# BLDC-CONTROLLET.net
KiCad netlist of a schematic drawn in Altium Designer
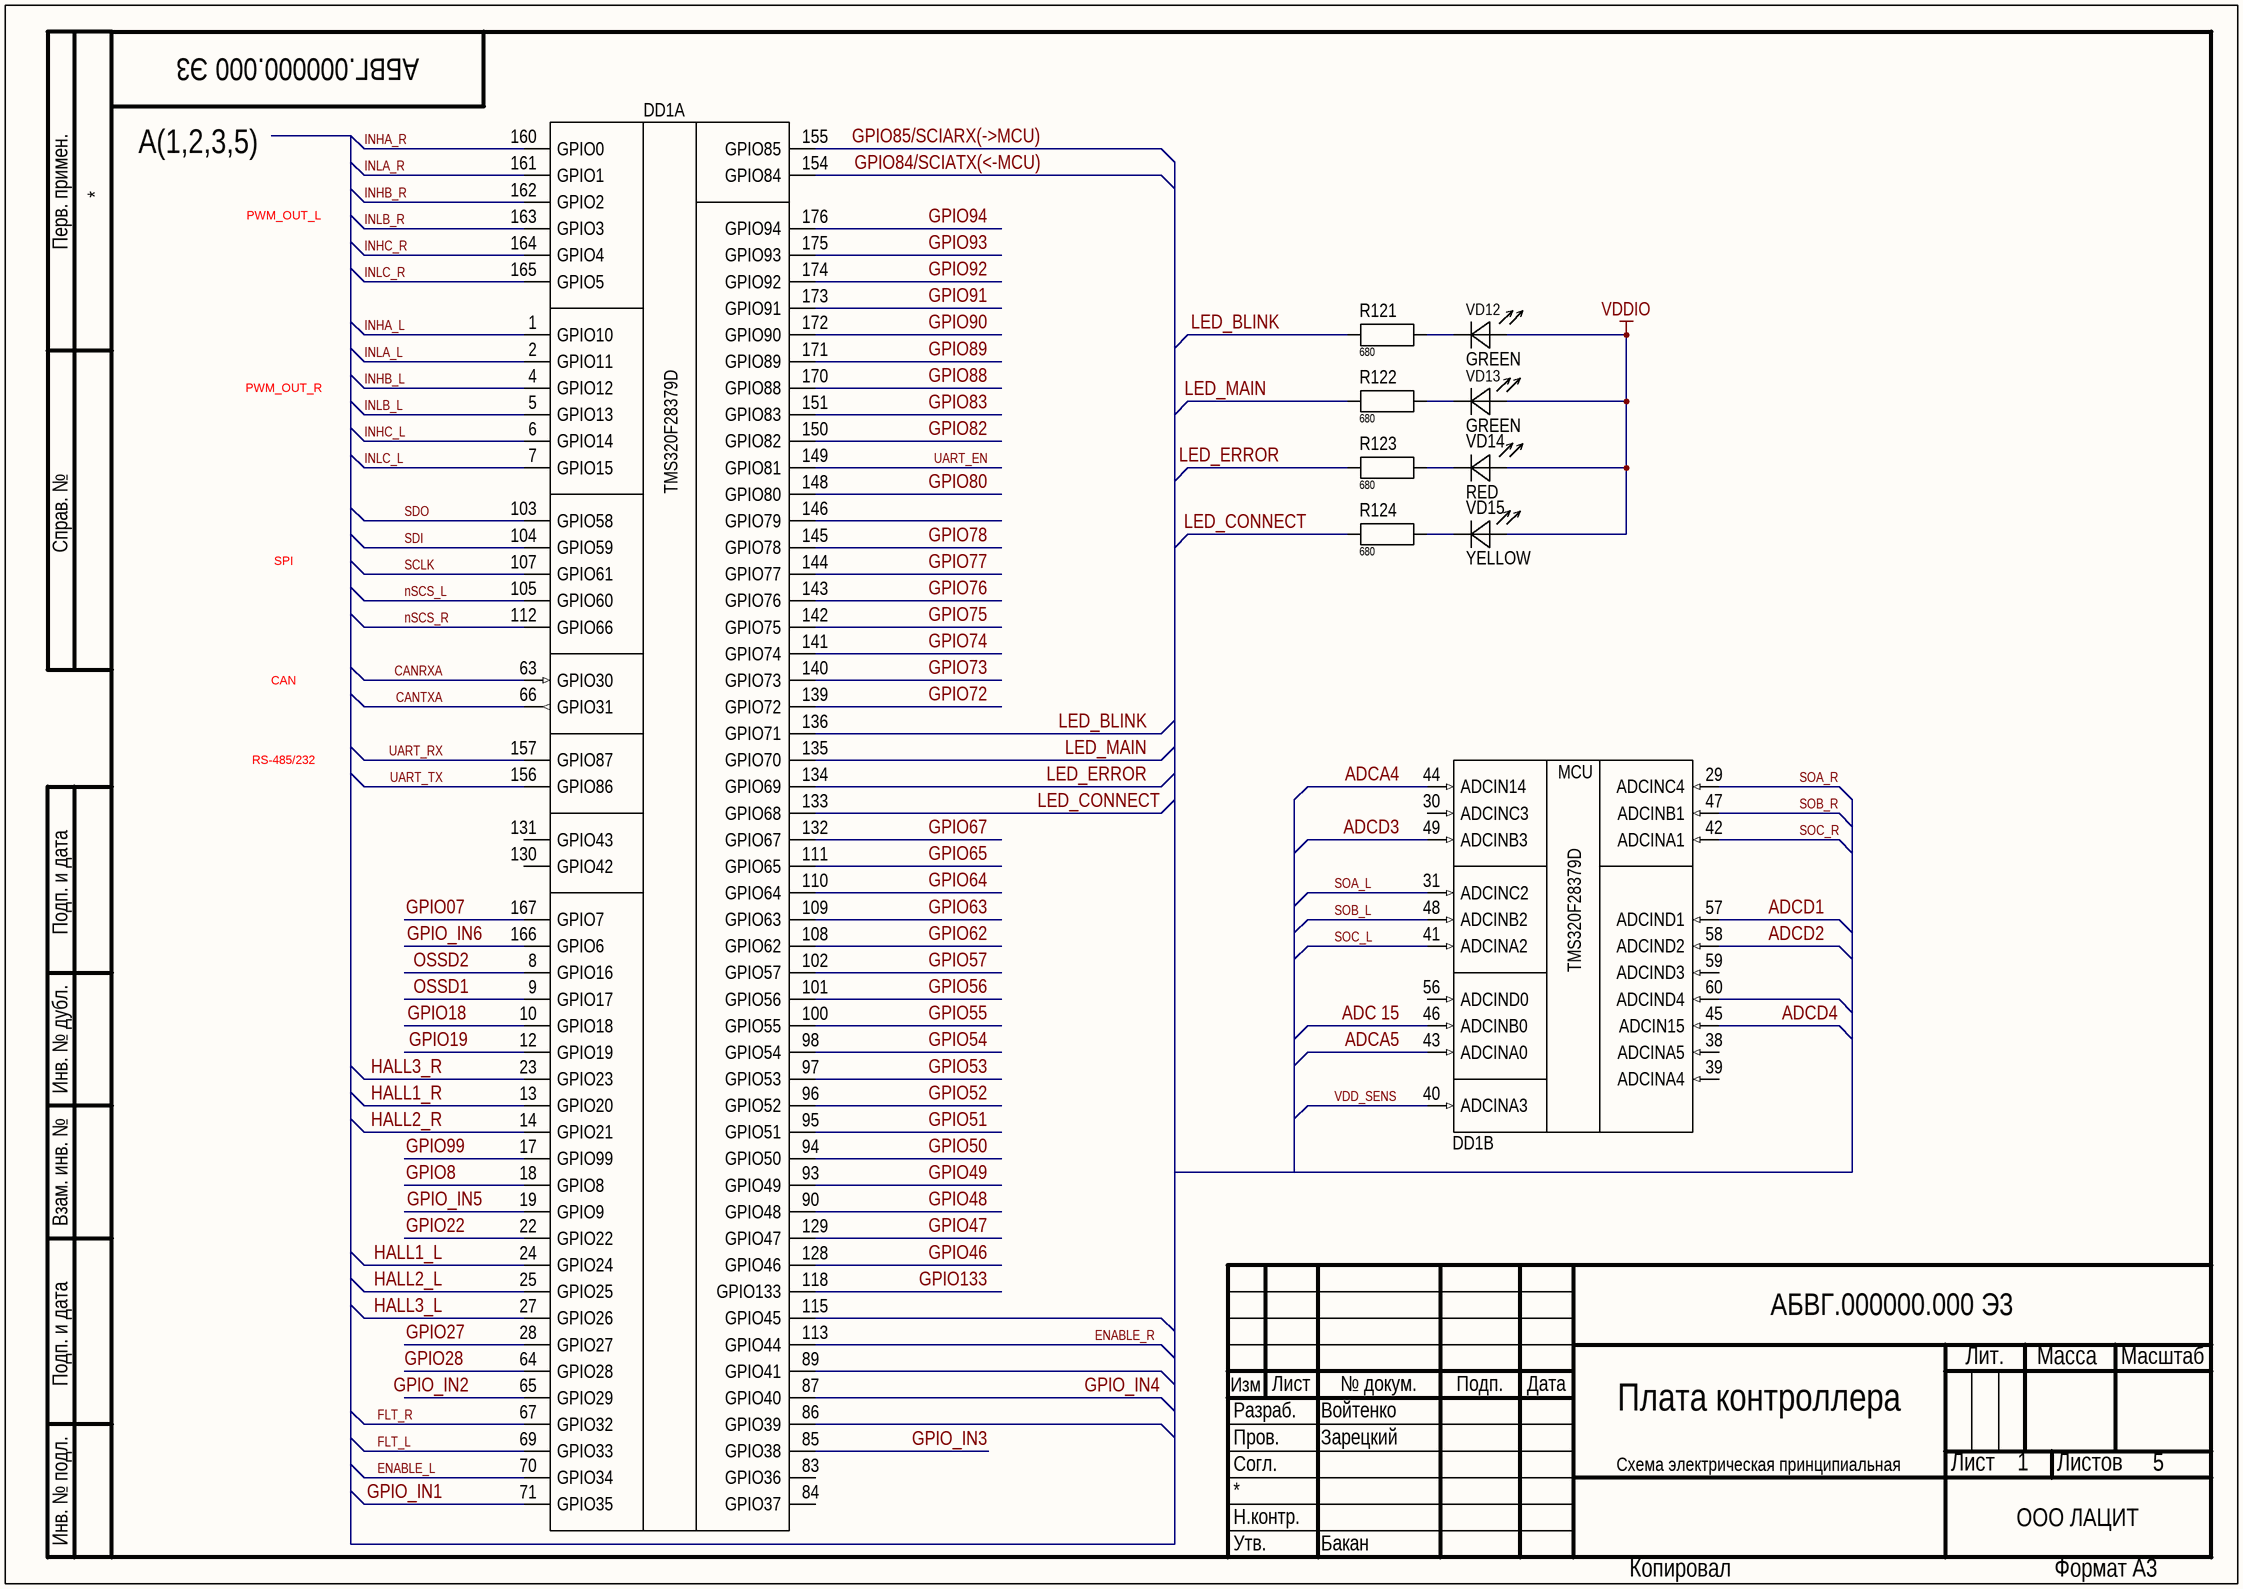
[diagram p0: BLDC-CONTROLLET.SchDoc]

(export (version "E")
  (design (tool "Eeschema 10.0.6"))
  (components
    (comp (ref "DD1")
      (value "TMS320F28379DPTP_LACID")
      (footprint "176-HLQFP")
      (fields (field (name "PARTNUMBER") "TMS320F28379DPTPT"))
      (libsource (lib "BKM_SCH_Lib") (part "TMS320F28379DPTP_LACID"))
    )
    (comp (ref "R121")
      (value "680")
      (footprint "RES: 0402")
      (fields (field (name "PARTNUMBER") "RC0402FR-07680RL"))
      (libsource (lib "Fider_Board_Lib") (part "RES 0402"))
    )
    (comp (ref "R122")
      (value "680")
      (footprint "RES: 0402")
      (fields (field (name "PARTNUMBER") "RC0402FR-07680RL"))
      (libsource (lib "Fider_Board_Lib") (part "RES 0402"))
    )
    (comp (ref "R123")
      (value "680")
      (footprint "RES: 0402")
      (fields (field (name "PARTNUMBER") "RC0402FR-07680RL"))
      (libsource (lib "Fider_Board_Lib") (part "RES 0402"))
    )
    (comp (ref "R124")
      (value "680")
      (footprint "RES: 0402")
      (fields (field (name "PARTNUMBER") "RC0402FR-07680RL"))
      (libsource (lib "Fider_Board_Lib") (part "RES 0402"))
    )
    (comp (ref "VD12")
      (value "GREEN")
      (footprint "LED: 0402G")
      (fields (field (name "Comment") "Led 0402 GREEN"))
      (libsource (lib "BKM_SCH_Lib") (part "Led 0402 GREEN"))
    )
    (comp (ref "VD13")
      (value "GREEN")
      (footprint "LED: 0402G")
      (fields (field (name "Comment") "Led 0402 GREEN"))
      (libsource (lib "BKM_SCH_Lib") (part "Led 0402 GREEN"))
    )
    (comp (ref "VD14")
      (value "RED")
      (footprint "LED: 0402R")
      (fields (field (name "Comment") "Led 0402 RED"))
      (libsource (lib "BKM_SCH_Lib") (part "Led 0402 RED"))
    )
    (comp (ref "VD15")
      (value "YELLOW")
      (footprint "LED: 0402Y")
      (fields (field (name "Comment") "Led 0402 YELLOW"))
      (libsource (lib "BKM_SCH_Lib") (part "Led 0402 YELLOW"))
    )
  )
  (nets
    (net (code "1") (name "/ADC 15") (class "Default")
      (node (ref "DD1") (pin "46") (pinfunction "ADCINB0_46") (pintype "input"))
    )
    (net (code "2") (name "/ADCA4") (class "Default")
      (node (ref "DD1") (pin "44") (pinfunction "ADCIN14_44") (pintype "input"))
    )
    (net (code "3") (name "/ADCA5") (class "Default")
      (node (ref "DD1") (pin "43") (pinfunction "ADCINA0_43") (pintype "input"))
    )
    (net (code "4") (name "/ADCD1") (class "Default")
      (node (ref "DD1") (pin "57") (pinfunction "ADCIND1_57") (pintype "input"))
    )
    (net (code "5") (name "/ADCD2") (class "Default")
      (node (ref "DD1") (pin "58") (pinfunction "ADCIND2_58") (pintype "input"))
    )
    (net (code "6") (name "/ADCD3") (class "Default")
      (node (ref "DD1") (pin "49") (pinfunction "ADCINB3_49") (pintype "input"))
    )
    (net (code "7") (name "/ADCD4") (class "Default")
      (node (ref "DD1") (pin "45") (pinfunction "ADCIN15_45") (pintype "input"))
    )
    (net (code "8") (name "/CANRXA") (class "Default")
      (node (ref "DD1") (pin "63") (pinfunction "GPIO30_63") (pintype "input"))
    )
    (net (code "9") (name "/CANTXA") (class "Default")
      (node (ref "DD1") (pin "66") (pinfunction "GPIO31_66") (pintype "output"))
    )
    (net (code "10") (name "/ENABLE_L") (class "Default")
      (node (ref "DD1") (pin "70") (pinfunction "GPIO34_70") (pintype "power_in"))
    )
    (net (code "11") (name "/ENABLE_R") (class "Default")
      (node (ref "DD1") (pin "113") (pinfunction "GPIO44_113") (pintype "power_in"))
    )
    (net (code "12") (name "/FLT_L") (class "Default")
      (node (ref "DD1") (pin "69") (pinfunction "GPIO33_69") (pintype "power_in"))
    )
    (net (code "13") (name "/FLT_R") (class "Default")
      (node (ref "DD1") (pin "67") (pinfunction "GPIO32_67") (pintype "power_in"))
    )
    (net (code "14") (name "/GPIO07") (class "Default")
      (node (ref "DD1") (pin "167") (pinfunction "GPIO7_167") (pintype "power_in"))
    )
    (net (code "15") (name "/GPIO8") (class "Default")
      (node (ref "DD1") (pin "18") (pinfunction "GPIO8_18") (pintype "power_in"))
    )
    (net (code "16") (name "/GPIO18") (class "Default")
      (node (ref "DD1") (pin "10") (pinfunction "GPIO18_10") (pintype "power_in"))
    )
    (net (code "17") (name "/GPIO19") (class "Default")
      (node (ref "DD1") (pin "12") (pinfunction "GPIO19_12") (pintype "power_in"))
    )
    (net (code "18") (name "/GPIO22") (class "Default")
      (node (ref "DD1") (pin "22") (pinfunction "GPIO22_22") (pintype "power_in"))
    )
    (net (code "19") (name "/GPIO27") (class "Default")
      (node (ref "DD1") (pin "28") (pinfunction "GPIO27_28") (pintype "power_in"))
    )
    (net (code "20") (name "/GPIO28") (class "Default")
      (node (ref "DD1") (pin "64") (pinfunction "GPIO28_64") (pintype "power_in"))
    )
    (net (code "21") (name "/GPIO46") (class "Default")
      (node (ref "DD1") (pin "128") (pinfunction "GPIO46_128") (pintype "power_in"))
    )
    (net (code "22") (name "/GPIO47") (class "Default")
      (node (ref "DD1") (pin "129") (pinfunction "GPIO47_129") (pintype "power_in"))
    )
    (net (code "23") (name "/GPIO48") (class "Default")
      (node (ref "DD1") (pin "90") (pinfunction "GPIO48_90") (pintype "power_in"))
    )
    (net (code "24") (name "/GPIO49") (class "Default")
      (node (ref "DD1") (pin "93") (pinfunction "GPIO49_93") (pintype "power_in"))
    )
    (net (code "25") (name "/GPIO50") (class "Default")
      (node (ref "DD1") (pin "94") (pinfunction "GPIO50_94") (pintype "power_in"))
    )
    (net (code "26") (name "/GPIO51") (class "Default")
      (node (ref "DD1") (pin "95") (pinfunction "GPIO51_95") (pintype "power_in"))
    )
    (net (code "27") (name "/GPIO52") (class "Default")
      (node (ref "DD1") (pin "96") (pinfunction "GPIO52_96") (pintype "power_in"))
    )
    (net (code "28") (name "/GPIO53") (class "Default")
      (node (ref "DD1") (pin "97") (pinfunction "GPIO53_97") (pintype "power_in"))
    )
    (net (code "29") (name "/GPIO54") (class "Default")
      (node (ref "DD1") (pin "98") (pinfunction "GPIO54_98") (pintype "power_in"))
    )
    (net (code "30") (name "/GPIO55") (class "Default")
      (node (ref "DD1") (pin "100") (pinfunction "GPIO55_100") (pintype "power_in"))
    )
    (net (code "31") (name "/GPIO56") (class "Default")
      (node (ref "DD1") (pin "101") (pinfunction "GPIO56_101") (pintype "power_in"))
    )
    (net (code "32") (name "/GPIO57") (class "Default")
      (node (ref "DD1") (pin "102") (pinfunction "GPIO57_102") (pintype "power_in"))
    )
    (net (code "33") (name "/GPIO62") (class "Default")
      (node (ref "DD1") (pin "108") (pinfunction "GPIO62_108") (pintype "power_in"))
    )
    (net (code "34") (name "/GPIO63") (class "Default")
      (node (ref "DD1") (pin "109") (pinfunction "GPIO63_109") (pintype "power_in"))
    )
    (net (code "35") (name "/GPIO64") (class "Default")
      (node (ref "DD1") (pin "110") (pinfunction "GPIO64_110") (pintype "power_in"))
    )
    (net (code "36") (name "/GPIO65") (class "Default")
      (node (ref "DD1") (pin "111") (pinfunction "GPIO65_111") (pintype "power_in"))
    )
    (net (code "37") (name "/GPIO67") (class "Default")
      (node (ref "DD1") (pin "132") (pinfunction "GPIO67_132") (pintype "power_in"))
    )
    (net (code "38") (name "/GPIO72") (class "Default")
      (node (ref "DD1") (pin "139") (pinfunction "GPIO72_139") (pintype "power_in"))
    )
    (net (code "39") (name "/GPIO73") (class "Default")
      (node (ref "DD1") (pin "140") (pinfunction "GPIO73_140") (pintype "power_in"))
    )
    (net (code "40") (name "/GPIO74") (class "Default")
      (node (ref "DD1") (pin "141") (pinfunction "GPIO74_141") (pintype "power_in"))
    )
    (net (code "41") (name "/GPIO75") (class "Default")
      (node (ref "DD1") (pin "142") (pinfunction "GPIO75_142") (pintype "power_in"))
    )
    (net (code "42") (name "/GPIO76") (class "Default")
      (node (ref "DD1") (pin "143") (pinfunction "GPIO76_143") (pintype "power_in"))
    )
    (net (code "43") (name "/GPIO77") (class "Default")
      (node (ref "DD1") (pin "144") (pinfunction "GPIO77_144") (pintype "power_in"))
    )
    (net (code "44") (name "/GPIO78") (class "Default")
      (node (ref "DD1") (pin "145") (pinfunction "GPIO78_145") (pintype "power_in"))
    )
    (net (code "45") (name "/GPIO80") (class "Default")
      (node (ref "DD1") (pin "148") (pinfunction "GPIO80_148") (pintype "power_in"))
    )
    (net (code "46") (name "/GPIO82") (class "Default")
      (node (ref "DD1") (pin "150") (pinfunction "GPIO82_150") (pintype "power_in"))
    )
    (net (code "47") (name "/GPIO83") (class "Default")
      (node (ref "DD1") (pin "151") (pinfunction "GPIO83_151") (pintype "power_in"))
    )
    (net (code "48") (name "/GPIO84{slash}SCIATX(<-MCU)") (class "Default")
      (node (ref "DD1") (pin "154") (pinfunction "GPIO84_154") (pintype "power_in"))
    )
    (net (code "49") (name "/GPIO85{slash}SCIARX(->MCU)") (class "Default")
      (node (ref "DD1") (pin "155") (pinfunction "GPIO85_155") (pintype "power_in"))
    )
    (net (code "50") (name "/GPIO88") (class "Default")
      (node (ref "DD1") (pin "170") (pinfunction "GPIO88_170") (pintype "power_in"))
    )
    (net (code "51") (name "/GPIO89") (class "Default")
      (node (ref "DD1") (pin "171") (pinfunction "GPIO89_171") (pintype "power_in"))
    )
    (net (code "52") (name "/GPIO90") (class "Default")
      (node (ref "DD1") (pin "172") (pinfunction "GPIO90_172") (pintype "power_in"))
    )
    (net (code "53") (name "/GPIO91") (class "Default")
      (node (ref "DD1") (pin "173") (pinfunction "GPIO91_173") (pintype "power_in"))
    )
    (net (code "54") (name "/GPIO92") (class "Default")
      (node (ref "DD1") (pin "174") (pinfunction "GPIO92_174") (pintype "power_in"))
    )
    (net (code "55") (name "/GPIO93") (class "Default")
      (node (ref "DD1") (pin "175") (pinfunction "GPIO93_175") (pintype "power_in"))
    )
    (net (code "56") (name "/GPIO94") (class "Default")
      (node (ref "DD1") (pin "176") (pinfunction "GPIO94_176") (pintype "power_in"))
    )
    (net (code "57") (name "/GPIO99") (class "Default")
      (node (ref "DD1") (pin "17") (pinfunction "GPIO99_17") (pintype "power_in"))
    )
    (net (code "58") (name "/GPIO133") (class "Default")
      (node (ref "DD1") (pin "118") (pinfunction "GPIO133_118") (pintype "power_in"))
    )
    (net (code "59") (name "/GPIO_IN1") (class "Default")
      (node (ref "DD1") (pin "71") (pinfunction "GPIO35_71") (pintype "power_in"))
    )
    (net (code "60") (name "/GPIO_IN2") (class "Default")
      (node (ref "DD1") (pin "65") (pinfunction "GPIO29_65") (pintype "power_in"))
    )
    (net (code "61") (name "/GPIO_IN3") (class "Default")
      (node (ref "DD1") (pin "85") (pinfunction "GPIO38_85") (pintype "power_in"))
    )
    (net (code "62") (name "/GPIO_IN4") (class "Default")
      (node (ref "DD1") (pin "87") (pinfunction "GPIO40_87") (pintype "power_in"))
    )
    (net (code "63") (name "/GPIO_IN5") (class "Default")
      (node (ref "DD1") (pin "19") (pinfunction "GPIO9_19") (pintype "power_in"))
    )
    (net (code "64") (name "/GPIO_IN6") (class "Default")
      (node (ref "DD1") (pin "166") (pinfunction "GPIO6_166") (pintype "power_in"))
    )
    (net (code "65") (name "/HALL1_L") (class "Default")
      (node (ref "DD1") (pin "24") (pinfunction "GPIO24_24") (pintype "power_in"))
    )
    (net (code "66") (name "/HALL1_R") (class "Default")
      (node (ref "DD1") (pin "13") (pinfunction "GPIO20_13") (pintype "power_in"))
    )
    (net (code "67") (name "/HALL2_L") (class "Default")
      (node (ref "DD1") (pin "25") (pinfunction "GPIO25_25") (pintype "power_in"))
    )
    (net (code "68") (name "/HALL2_R") (class "Default")
      (node (ref "DD1") (pin "14") (pinfunction "GPIO21_14") (pintype "power_in"))
    )
    (net (code "69") (name "/HALL3_L") (class "Default")
      (node (ref "DD1") (pin "27") (pinfunction "GPIO26_27") (pintype "power_in"))
    )
    (net (code "70") (name "/HALL3_R") (class "Default")
      (node (ref "DD1") (pin "23") (pinfunction "GPIO23_23") (pintype "power_in"))
    )
    (net (code "71") (name "/INHA_L") (class "Default")
      (node (ref "DD1") (pin "1") (pinfunction "GPIO10_1") (pintype "power_in"))
    )
    (net (code "72") (name "/INHA_R") (class "Default")
      (node (ref "DD1") (pin "160") (pinfunction "GPIO0_160") (pintype "power_in"))
    )
    (net (code "73") (name "/INHB_L") (class "Default")
      (node (ref "DD1") (pin "4") (pinfunction "GPIO12_4") (pintype "power_in"))
    )
    (net (code "74") (name "/INHB_R") (class "Default")
      (node (ref "DD1") (pin "162") (pinfunction "GPIO2_162") (pintype "power_in"))
    )
    (net (code "75") (name "/INHC_L") (class "Default")
      (node (ref "DD1") (pin "6") (pinfunction "GPIO14_6") (pintype "power_in"))
    )
    (net (code "76") (name "/INHC_R") (class "Default")
      (node (ref "DD1") (pin "164") (pinfunction "GPIO4_164") (pintype "power_in"))
    )
    (net (code "77") (name "/INLA_L") (class "Default")
      (node (ref "DD1") (pin "2") (pinfunction "GPIO11_2") (pintype "power_in"))
    )
    (net (code "78") (name "/INLA_R") (class "Default")
      (node (ref "DD1") (pin "161") (pinfunction "GPIO1_161") (pintype "power_in"))
    )
    (net (code "79") (name "/INLB_L") (class "Default")
      (node (ref "DD1") (pin "5") (pinfunction "GPIO13_5") (pintype "power_in"))
    )
    (net (code "80") (name "/INLB_R") (class "Default")
      (node (ref "DD1") (pin "163") (pinfunction "GPIO3_163") (pintype "power_in"))
    )
    (net (code "81") (name "/INLC_L") (class "Default")
      (node (ref "DD1") (pin "7") (pinfunction "GPIO15_7") (pintype "power_in"))
    )
    (net (code "82") (name "/INLC_R") (class "Default")
      (node (ref "DD1") (pin "165") (pinfunction "GPIO5_165") (pintype "power_in"))
    )
    (net (code "83") (name "/LED_BLINK") (class "Default")
      (node (ref "DD1") (pin "136") (pinfunction "GPIO71_136") (pintype "power_in"))
      (node (ref "R121") (pin "1") (pinfunction "1_1") (pintype "passive"))
    )
    (net (code "84") (name "/LED_CONNECT") (class "Default")
      (node (ref "DD1") (pin "133") (pinfunction "GPIO68_133") (pintype "power_in"))
      (node (ref "R124") (pin "1") (pinfunction "1_1") (pintype "passive"))
    )
    (net (code "85") (name "/LED_ERROR") (class "Default")
      (node (ref "DD1") (pin "134") (pinfunction "GPIO69_134") (pintype "power_in"))
      (node (ref "R123") (pin "1") (pinfunction "1_1") (pintype "passive"))
    )
    (net (code "86") (name "/LED_MAIN") (class "Default")
      (node (ref "DD1") (pin "135") (pinfunction "GPIO70_135") (pintype "power_in"))
      (node (ref "R122") (pin "1") (pinfunction "1_1") (pintype "passive"))
    )
    (net (code "87") (name "/OSSD1") (class "Default")
      (node (ref "DD1") (pin "9") (pinfunction "GPIO17_9") (pintype "power_in"))
    )
    (net (code "88") (name "/OSSD2") (class "Default")
      (node (ref "DD1") (pin "8") (pinfunction "GPIO16_8") (pintype "power_in"))
    )
    (net (code "89") (name "/SCLK") (class "Default")
      (node (ref "DD1") (pin "107") (pinfunction "GPIO61_107") (pintype "power_in"))
    )
    (net (code "90") (name "/SDI") (class "Default")
      (node (ref "DD1") (pin "104") (pinfunction "GPIO59_104") (pintype "power_in"))
    )
    (net (code "91") (name "/SDO") (class "Default")
      (node (ref "DD1") (pin "103") (pinfunction "GPIO58_103") (pintype "power_in"))
    )
    (net (code "92") (name "/SOA_L") (class "Default")
      (node (ref "DD1") (pin "31") (pinfunction "ADCINС2_31") (pintype "input"))
    )
    (net (code "93") (name "/SOA_R") (class "Default")
      (node (ref "DD1") (pin "29") (pinfunction "ADCINC4_29") (pintype "input"))
    )
    (net (code "94") (name "/SOB_L") (class "Default")
      (node (ref "DD1") (pin "48") (pinfunction "ADCINB2_48") (pintype "input"))
    )
    (net (code "95") (name "/SOB_R") (class "Default")
      (node (ref "DD1") (pin "47") (pinfunction "ADCINB1_47") (pintype "input"))
    )
    (net (code "96") (name "/SOC_L") (class "Default")
      (node (ref "DD1") (pin "41") (pinfunction "ADCINA2_41") (pintype "input"))
    )
    (net (code "97") (name "/SOC_R") (class "Default")
      (node (ref "DD1") (pin "42") (pinfunction "ADCINA1_42") (pintype "input"))
    )
    (net (code "98") (name "/UART_EN") (class "Default")
      (node (ref "DD1") (pin "149") (pinfunction "GPIO81_149") (pintype "power_in"))
    )
    (net (code "99") (name "/UART_RX") (class "Default")
      (node (ref "DD1") (pin "157") (pinfunction "GPIO87_157") (pintype "power_in"))
    )
    (net (code "100") (name "/UART_TX") (class "Default")
      (node (ref "DD1") (pin "156") (pinfunction "GPIO86_156") (pintype "power_in"))
    )
    (net (code "101") (name "/VDD_SENS") (class "Default")
      (node (ref "DD1") (pin "40") (pinfunction "ADCINA3_40") (pintype "input"))
    )
    (net (code "102") (name "/nSCS_L") (class "Default")
      (node (ref "DD1") (pin "105") (pinfunction "GPIO60_105") (pintype "power_in"))
    )
    (net (code "103") (name "/nSCS_R") (class "Default")
      (node (ref "DD1") (pin "112") (pinfunction "GPIO66_112") (pintype "power_in"))
    )
    (net (code "104") (name "Net-(R121-Pad2)") (class "Default")
      (node (ref "R121") (pin "2") (pinfunction "2_2") (pintype "passive"))
      (node (ref "VD12") (pin "2") (pinfunction "2_2") (pintype "passive"))
    )
    (net (code "105") (name "Net-(R122-Pad2)") (class "Default")
      (node (ref "R122") (pin "2") (pinfunction "2_2") (pintype "passive"))
      (node (ref "VD13") (pin "2") (pinfunction "2_2") (pintype "passive"))
    )
    (net (code "106") (name "Net-(R123-Pad2)") (class "Default")
      (node (ref "R123") (pin "2") (pinfunction "2_2") (pintype "passive"))
      (node (ref "VD14") (pin "2") (pinfunction "2_2") (pintype "passive"))
    )
    (net (code "107") (name "Net-(R124-Pad2)") (class "Default")
      (node (ref "R124") (pin "2") (pinfunction "2_2") (pintype "passive"))
      (node (ref "VD15") (pin "2") (pinfunction "2_2") (pintype "passive"))
    )
    (net (code "108") (name "VDDIO") (class "Default")
      (node (ref "VD12") (pin "1") (pinfunction "1_1") (pintype "passive"))
      (node (ref "VD13") (pin "1") (pinfunction "1_1") (pintype "passive"))
      (node (ref "VD14") (pin "1") (pinfunction "1_1") (pintype "passive"))
      (node (ref "VD15") (pin "1") (pinfunction "1_1") (pintype "passive"))
    )
    (net (code "109") (name "unconnected-(DD1A-GPIO36-Pad83)") (class "Default")
      (node (ref "DD1") (pin "83") (pinfunction "GPIO36_83") (pintype "power_in"))
    )
    (net (code "110") (name "unconnected-(DD1A-GPIO37-Pad84)") (class "Default")
      (node (ref "DD1") (pin "84") (pinfunction "GPIO37_84") (pintype "power_in"))
    )
    (net (code "111") (name "unconnected-(DD1A-GPIO39-Pad86)") (class "Default")
      (node (ref "DD1") (pin "86") (pinfunction "GPIO39_86") (pintype "power_in"))
    )
    (net (code "112") (name "unconnected-(DD1A-GPIO41-Pad89)") (class "Default")
      (node (ref "DD1") (pin "89") (pinfunction "GPIO41_89") (pintype "power_in"))
    )
    (net (code "113") (name "unconnected-(DD1A-GPIO42-Pad130)") (class "Default")
      (node (ref "DD1") (pin "130") (pinfunction "GPIO42_130") (pintype "power_in"))
    )
    (net (code "114") (name "unconnected-(DD1A-GPIO43-Pad131)") (class "Default")
      (node (ref "DD1") (pin "131") (pinfunction "GPIO43_131") (pintype "power_in"))
    )
    (net (code "115") (name "unconnected-(DD1A-GPIO45-Pad115)") (class "Default")
      (node (ref "DD1") (pin "115") (pinfunction "GPIO45_115") (pintype "power_in"))
    )
    (net (code "116") (name "unconnected-(DD1A-GPIO79-Pad146)") (class "Default")
      (node (ref "DD1") (pin "146") (pinfunction "GPIO79_146") (pintype "power_in"))
    )
    (net (code "117") (name "unconnected-(DD1B-ADCINA4-Pad39)") (class "Default")
      (node (ref "DD1") (pin "39") (pinfunction "ADCINA4_39") (pintype "input"))
    )
    (net (code "118") (name "unconnected-(DD1B-ADCINA5-Pad38)") (class "Default")
      (node (ref "DD1") (pin "38") (pinfunction "ADCINA5_38") (pintype "input"))
    )
    (net (code "119") (name "unconnected-(DD1B-ADCINC3-Pad30)") (class "Default")
      (node (ref "DD1") (pin "30") (pinfunction "ADCINC3_30") (pintype "input"))
    )
    (net (code "120") (name "unconnected-(DD1B-ADCIND0-Pad56)") (class "Default")
      (node (ref "DD1") (pin "56") (pinfunction "ADCIND0_56") (pintype "input"))
    )
    (net (code "121") (name "unconnected-(DD1B-ADCIND3-Pad59)") (class "Default")
      (node (ref "DD1") (pin "59") (pinfunction "ADCIND3_59") (pintype "input"))
    )
    (net (code "122") (name "unconnected-(DD1B-ADCIND4-Pad60)") (class "Default")
      (node (ref "DD1") (pin "60") (pinfunction "ADCIND4_60") (pintype "input"))
    )
  )
)
